# LM338_PSU_RevC.net
KiCad netlist of a schematic drawn in EAGLE
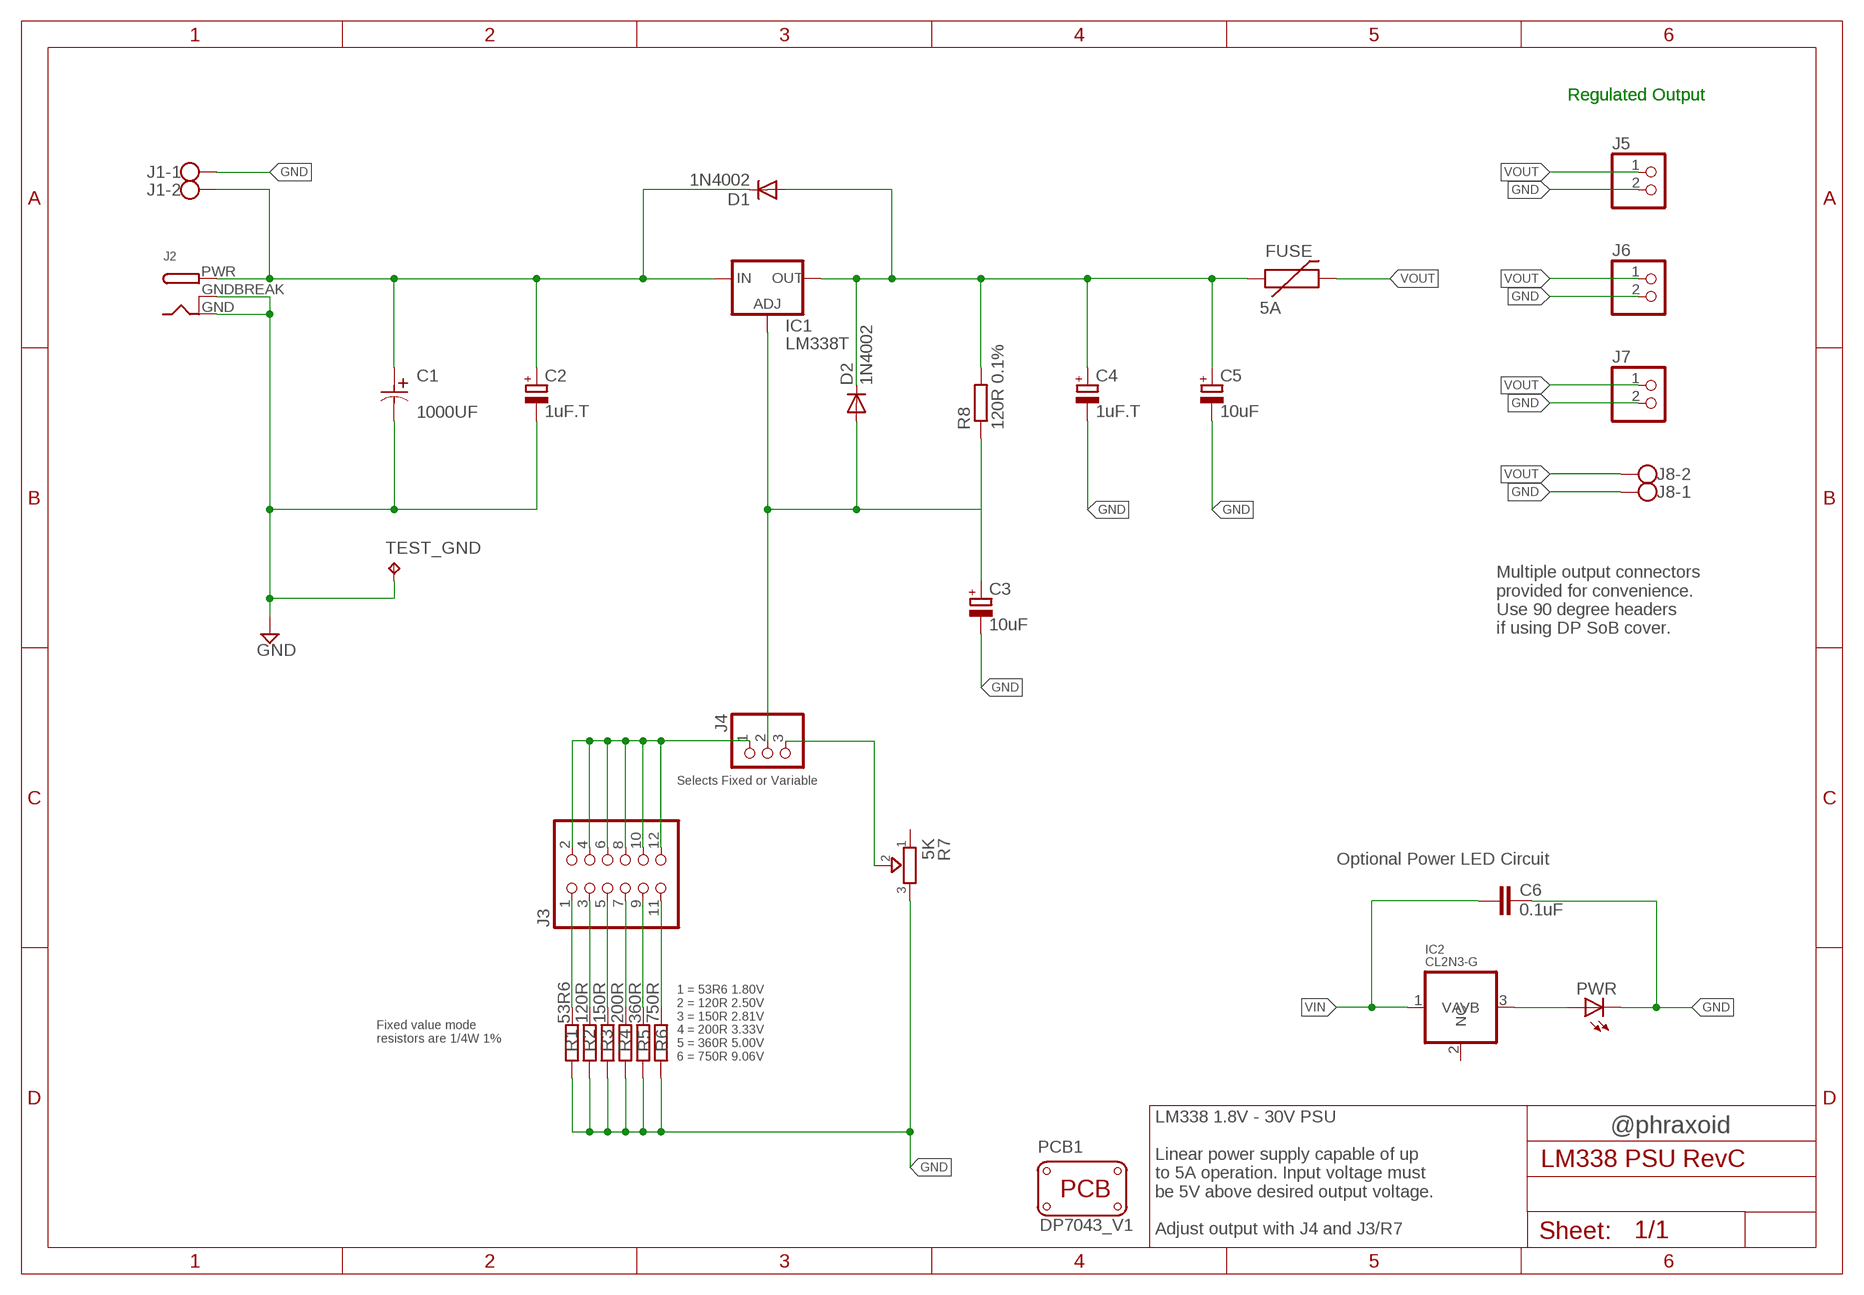
[diagram p0: schematic, sheet 1]

(export (version "E")
  (design (tool "Eeschema 10.0.6"))
  (components
    (comp (ref "C1")
      (value "1000UF")
      (footprint "eagle-import:CAPPR500-1250X2500")
      (fields
        (field (name "MPN") "ECA1HHG102")
        (field (name "TOLERANCE") "±20 %")
        (field (name "MF") "PANASONIC")
        (field (name "MPN_1") "ECA1HM102")
        (field (name "OC_FARNELL") "9693823")
      )
      (libsource (lib "eagle-import") (part "ECA-D12.5XP51HHG102"))
    )
    (comp (ref "C2")
      (value "1uF.T")
      (footprint "eagle-import:E5-4")
      (libsource (lib "eagle-import") (part "CPOL-EUE5-4"))
    )
    (comp (ref "C3")
      (value "10uF")
      (footprint "eagle-import:E2,5-7")
      (fields (field (name "MF") "PANASONIC") (field (name "MPN") "ECEA1HN100U"))
      (libsource (lib "eagle-import") (part "CPOL-EUE2.5-7"))
    )
    (comp (ref "C4")
      (value "1uF.T")
      (footprint "eagle-import:E5-4")
      (libsource (lib "eagle-import") (part "CPOL-EUE5-4"))
    )
    (comp (ref "C5")
      (value "10uF")
      (footprint "eagle-import:E2,5-7")
      (fields (field (name "MF") "PANASONIC") (field (name "MPN") "ECEA1HN100U"))
      (libsource (lib "eagle-import") (part "CPOL-EUE2.5-7"))
    )
    (comp (ref "C6")
      (value "0.1uF")
      (footprint "eagle-import:C025-025X050")
      (fields (field (name "MF") "AVX") (field (name "MPN") "02016D104KAT2A"))
      (libsource (lib "eagle-import") (part "C-EU025-025X050"))
    )
    (comp (ref "D1")
      (value "1N4002")
      (footprint "eagle-import:DO41-10")
      (fields (field (name "MF") "ON SEMICONDUCTOR") (field (name "MPN") "1N4002RLG"))
      (libsource (lib "eagle-import") (part "1N4004"))
    )
    (comp (ref "D2")
      (value "1N4002")
      (footprint "eagle-import:DO41-10")
      (fields (field (name "MF") "ON SEMICONDUCTOR") (field (name "MPN") "1N4002RLG"))
      (libsource (lib "eagle-import") (part "1N4004"))
    )
    (comp (ref "FUSE")
      (value "5A")
      (footprint "eagle-import:PTC")
      (fields (field (name "MF") "LITTELFUSE") (field (name "MPN") "30R400UF"))
      (libsource (lib "eagle-import") (part "PTCPTH"))
    )
    (comp (ref "IC1")
      (value "LM338T")
      (footprint "eagle-import:TO220-ADJ")
      (fields (field (name "MF") "TEXAS INSTRUMENTS") (field (name "MPN") "LM338T/NOPB"))
      (libsource (lib "eagle-import") (part "V_REG_317SINK"))
    )
    (comp (ref "IC2")
      (value "CL2N3-G")
      (footprint "eagle-import:TO-92")
      (libsource (lib "eagle-import") (part "CL2N3-G"))
    )
    (comp (ref "J1")
      (value "W237-102")
      (footprint "eagle-import:W237-102")
      (fields
        (field (name "MPN") "237-102")
        (field (name "MF") "MULTICOMP")
        (field (name "MPN_1") "MC000048")
        (field (name "OC_FARNELL") "2008019")
      )
      (libsource (lib "eagle-import") (part "W237-102"))
    )
    (comp (ref "J2")
      (value "DCBARRELPTH")
      (footprint "eagle-import:DCJACK_2MM_PTH")
      (libsource (lib "eagle-import") (part "DCBARRELPTH"))
    )
    (comp (ref "J3")
      (value "PINHD-2X6")
      (footprint "eagle-import:2X06")
      (libsource (lib "eagle-import") (part "PINHD-2X6"))
    )
    (comp (ref "J4")
      (value "PINHD-1X3/90")
      (footprint "eagle-import:1X03_90")
      (fields (field (name "MF") "MULTICOMP") (field (name "MPN") "MC34747"))
      (libsource (lib "eagle-import") (part "PINHD-1X3/90"))
    )
    (comp (ref "J5")
      (value "PINHD-1X2/90")
      (footprint "eagle-import:1X02_90")
      (fields (field (name "MF") "MULTICOMP") (field (name "MPN") "MC34745"))
      (libsource (lib "eagle-import") (part "PINHD-1X2/90"))
    )
    (comp (ref "J6")
      (value "PINHD-1X2/90")
      (footprint "eagle-import:1X02_90")
      (fields (field (name "MF") "MULTICOMP") (field (name "MPN") "MC34745"))
      (libsource (lib "eagle-import") (part "PINHD-1X2/90"))
    )
    (comp (ref "J7")
      (value "PINHD-1X2/90")
      (footprint "eagle-import:1X02_90")
      (fields (field (name "MF") "MULTICOMP") (field (name "MPN") "MC34745"))
      (libsource (lib "eagle-import") (part "PINHD-1X2/90"))
    )
    (comp (ref "J8")
      (value "W237-102")
      (footprint "eagle-import:W237-102")
      (fields
        (field (name "MPN") "237-102")
        (field (name "MF") "MULTICOMP")
        (field (name "MPN_1") "MC000048")
        (field (name "OC_FARNELL") "2008019")
      )
      (libsource (lib "eagle-import") (part "W237-102"))
    )
    (comp (ref "PCB1")
      (value "PCB_DP_RECTANGLE-43X70")
      (footprint "eagle-import:DP7043_V1")
      (libsource (lib "eagle-import") (part "PCB_DP_RECTANGLE-43X70"))
    )
    (comp (ref "PWR")
      (value "LED5MM")
      (footprint "eagle-import:LED5MM")
      (fields (field (name "MF") "CREE") (field (name "MPN") "C503B-RBN-CX0Y0AA1"))
      (libsource (lib "eagle-import") (part "LED5MM"))
    )
    (comp (ref "R1")
      (value "53R6")
      (footprint "eagle-import:0207_10")
      (fields (field (name "MF") "TE CONNECTIVITY / HOLSWORTHY") (field (name "MPN") "H853R6BYA"))
      (libsource (lib "eagle-import") (part "R-EU_0207/10"))
    )
    (comp (ref "R2")
      (value "120R")
      (footprint "eagle-import:0207_10")
      (fields (field (name "MF") "WELWYN") (field (name "MPN") "PR5Y-120RBI"))
      (libsource (lib "eagle-import") (part "R-EU_0207/10"))
    )
    (comp (ref "R3")
      (value "150R")
      (footprint "eagle-import:0207_10")
      (fields (field (name "MF") "TE CONNECTIVITY / HOLSWORTHY") (field (name "MPN") "H8150RBYA"))
      (libsource (lib "eagle-import") (part "R-EU_0207/10"))
    )
    (comp (ref "R4")
      (value "200R")
      (footprint "eagle-import:0207_10")
      (fields (field (name "MF") "TE CONNECTIVITY / HOLSWORTHY") (field (name "MPN") "H8200RBYA"))
      (libsource (lib "eagle-import") (part "R-EU_0207/10"))
    )
    (comp (ref "R5")
      (value "360R")
      (footprint "eagle-import:0207_10")
      (fields (field (name "MF") "MULTICOMP") (field (name "MPN") "MF25 360R"))
      (libsource (lib "eagle-import") (part "R-EU_0207/10"))
    )
    (comp (ref "R6")
      (value "750R")
      (footprint "eagle-import:0207_10")
      (fields (field (name "MF") "TE CONNECTIVITY / HOLSWORTHY") (field (name "MPN") "H8750RBYA"))
      (libsource (lib "eagle-import") (part "R-EU_0207/10"))
    )
    (comp (ref "R7")
      (value "5K")
      (footprint "eagle-import:TRIMMER_3362P")
      (fields (field (name "MF") "BOURNS") (field (name "MPN") "3362P-1-502LF"))
      (libsource (lib "eagle-import") (part "TRIMMER-3362P"))
    )
    (comp (ref "R8")
      (value "120R 0.1%")
      (footprint "eagle-import:0207_10")
      (fields (field (name "MF") "MULTICOMP") (field (name "MPN") "MF25 120R"))
      (libsource (lib "eagle-import") (part "R-EU_0207/10"))
    )
    (comp (ref "TEST_GND")
      (value "TPPAD1-13")
      (footprint "eagle-import:P1-13")
      (libsource (lib "eagle-import") (part "TPPAD1-13"))
    )
  )
  (nets
    (net (code "1") (name "GND") (class "Default")
      (node (ref "C1") (pin "2") (pinfunction "2_2") (pintype "passive"))
      (node (ref "C2") (pin "-") (pinfunction "-_-") (pintype "passive"))
      (node (ref "C3") (pin "-") (pinfunction "-_-") (pintype "passive"))
      (node (ref "C4") (pin "-") (pinfunction "-_-") (pintype "passive"))
      (node (ref "C5") (pin "-") (pinfunction "-_-") (pintype "passive"))
      (node (ref "C6") (pin "2") (pinfunction "2_2") (pintype "passive"))
      (node (ref "J1") (pin "1") (pinfunction "KL_1") (pintype "passive"))
      (node (ref "J2") (pin "GND") (pinfunction "GND_GND") (pintype "power_in"))
      (node (ref "J2") (pin "GNDBREAK") (pinfunction "GNDBREAK_GNDBREAK") (pintype "power_in"))
      (node (ref "J5") (pin "2") (pinfunction "2_2") (pintype "passive"))
      (node (ref "J6") (pin "2") (pinfunction "2_2") (pintype "passive"))
      (node (ref "J7") (pin "2") (pinfunction "2_2") (pintype "passive"))
      (node (ref "J8") (pin "1") (pinfunction "KL_1") (pintype "passive"))
      (node (ref "PWR") (pin "K") (pinfunction "C_K") (pintype "passive"))
      (node (ref "R1") (pin "1") (pinfunction "1_1") (pintype "passive"))
      (node (ref "R2") (pin "1") (pinfunction "1_1") (pintype "passive"))
      (node (ref "R3") (pin "1") (pinfunction "1_1") (pintype "passive"))
      (node (ref "R4") (pin "1") (pinfunction "1_1") (pintype "passive"))
      (node (ref "R5") (pin "1") (pinfunction "1_1") (pintype "passive"))
      (node (ref "R6") (pin "1") (pinfunction "1_1") (pintype "passive"))
      (node (ref "R7") (pin "3") (pinfunction "3_3") (pintype "passive"))
      (node (ref "TEST_GND") (pin "TP") (pinfunction "TP_TP") (pintype "input"))
    )
    (net (code "2") (name "Net-(C3-Pad+)") (class "Default")
      (node (ref "C3") (pin "+") (pinfunction "+_+") (pintype "passive"))
      (node (ref "D2") (pin "A") (pinfunction "A_A") (pintype "passive"))
      (node (ref "IC1") (pin "ADJ") (pinfunction "ADJ_ADJ") (pintype "input"))
      (node (ref "J4") (pin "2") (pinfunction "2_2") (pintype "passive"))
      (node (ref "R8") (pin "1") (pinfunction "1_1") (pintype "passive"))
    )
    (net (code "3") (name "Net-(FUSE-1)") (class "Default")
      (node (ref "C4") (pin "+") (pinfunction "+_+") (pintype "passive"))
      (node (ref "C5") (pin "+") (pinfunction "+_+") (pintype "passive"))
      (node (ref "D1") (pin "A") (pinfunction "A_A") (pintype "passive"))
      (node (ref "D2") (pin "C") (pinfunction "C_C") (pintype "passive"))
      (node (ref "FUSE") (pin "P$1") (pinfunction "1_P$1") (pintype "bidirectional"))
      (node (ref "IC1") (pin "OUT") (pinfunction "OUT_OUT") (pintype "output"))
      (node (ref "R8") (pin "2") (pinfunction "2_2") (pintype "passive"))
    )
    (net (code "4") (name "Net-(IC2-VB)") (class "Default")
      (node (ref "IC2") (pin "3") (pinfunction "VB_3") (pintype "power_in"))
      (node (ref "PWR") (pin "A") (pinfunction "A_A") (pintype "passive"))
    )
    (net (code "5") (name "Net-(J3-Pad1)") (class "Default")
      (node (ref "J3") (pin "1") (pinfunction "1_1") (pintype "passive"))
      (node (ref "R1") (pin "2") (pinfunction "2_2") (pintype "passive"))
    )
    (net (code "6") (name "Net-(J3-Pad3)") (class "Default")
      (node (ref "J3") (pin "3") (pinfunction "3_3") (pintype "passive"))
      (node (ref "R2") (pin "2") (pinfunction "2_2") (pintype "passive"))
    )
    (net (code "7") (name "Net-(J3-Pad5)") (class "Default")
      (node (ref "J3") (pin "5") (pinfunction "5_5") (pintype "passive"))
      (node (ref "R3") (pin "2") (pinfunction "2_2") (pintype "passive"))
    )
    (net (code "8") (name "Net-(J3-Pad7)") (class "Default")
      (node (ref "J3") (pin "7") (pinfunction "7_7") (pintype "passive"))
      (node (ref "R4") (pin "2") (pinfunction "2_2") (pintype "passive"))
    )
    (net (code "9") (name "Net-(J3-Pad9)") (class "Default")
      (node (ref "J3") (pin "9") (pinfunction "9_9") (pintype "passive"))
      (node (ref "R5") (pin "2") (pinfunction "2_2") (pintype "passive"))
    )
    (net (code "10") (name "Net-(J3-Pad10)") (class "Default")
      (node (ref "J3") (pin "10") (pinfunction "10_10") (pintype "passive"))
      (node (ref "J3") (pin "12") (pinfunction "12_12") (pintype "passive"))
      (node (ref "J3") (pin "2") (pinfunction "2_2") (pintype "passive"))
      (node (ref "J3") (pin "4") (pinfunction "4_4") (pintype "passive"))
      (node (ref "J3") (pin "6") (pinfunction "6_6") (pintype "passive"))
      (node (ref "J3") (pin "8") (pinfunction "8_8") (pintype "passive"))
      (node (ref "J4") (pin "1") (pinfunction "1_1") (pintype "passive"))
    )
    (net (code "11") (name "Net-(J3-Pad11)") (class "Default")
      (node (ref "J3") (pin "11") (pinfunction "11_11") (pintype "passive"))
      (node (ref "R6") (pin "2") (pinfunction "2_2") (pintype "passive"))
    )
    (net (code "12") (name "Net-(J4-Pad3)") (class "Default")
      (node (ref "J4") (pin "3") (pinfunction "3_3") (pintype "passive"))
      (node (ref "R7") (pin "2") (pinfunction "2_2") (pintype "passive"))
    )
    (net (code "13") (name "VIN") (class "Default")
      (node (ref "C1") (pin "1") (pinfunction "1_1") (pintype "passive"))
      (node (ref "C2") (pin "+") (pinfunction "+_+") (pintype "passive"))
      (node (ref "C6") (pin "1") (pinfunction "1_1") (pintype "passive"))
      (node (ref "D1") (pin "C") (pinfunction "C_C") (pintype "passive"))
      (node (ref "IC1") (pin "IN") (pinfunction "IN_IN") (pintype "input"))
      (node (ref "IC2") (pin "1") (pinfunction "VA_1") (pintype "power_in"))
      (node (ref "J1") (pin "2") (pinfunction "KL_2") (pintype "passive"))
      (node (ref "J2") (pin "PWR") (pinfunction "PWR_PWR") (pintype "power_in"))
    )
    (net (code "14") (name "VOUT") (class "Default")
      (node (ref "FUSE") (pin "P$2") (pinfunction "2_P$2") (pintype "bidirectional"))
      (node (ref "J5") (pin "1") (pinfunction "1_1") (pintype "passive"))
      (node (ref "J6") (pin "1") (pinfunction "1_1") (pintype "passive"))
      (node (ref "J7") (pin "1") (pinfunction "1_1") (pintype "passive"))
      (node (ref "J8") (pin "2") (pinfunction "KL_2") (pintype "passive"))
    )
    (net (code "15") (name "unconnected-(IC2-NC-Pad2)") (class "Default")
      (node (ref "IC2") (pin "2") (pinfunction "NC_2") (pintype "no_connect"))
    )
    (net (code "16") (name "unconnected-(R7-Pad1)") (class "Default")
      (node (ref "R7") (pin "1") (pinfunction "1_1") (pintype "passive"))
    )
  )
)
